# Arduino-Pro-Mini_Silk_1.net
KiCad netlist of a schematic drawn in EAGLE
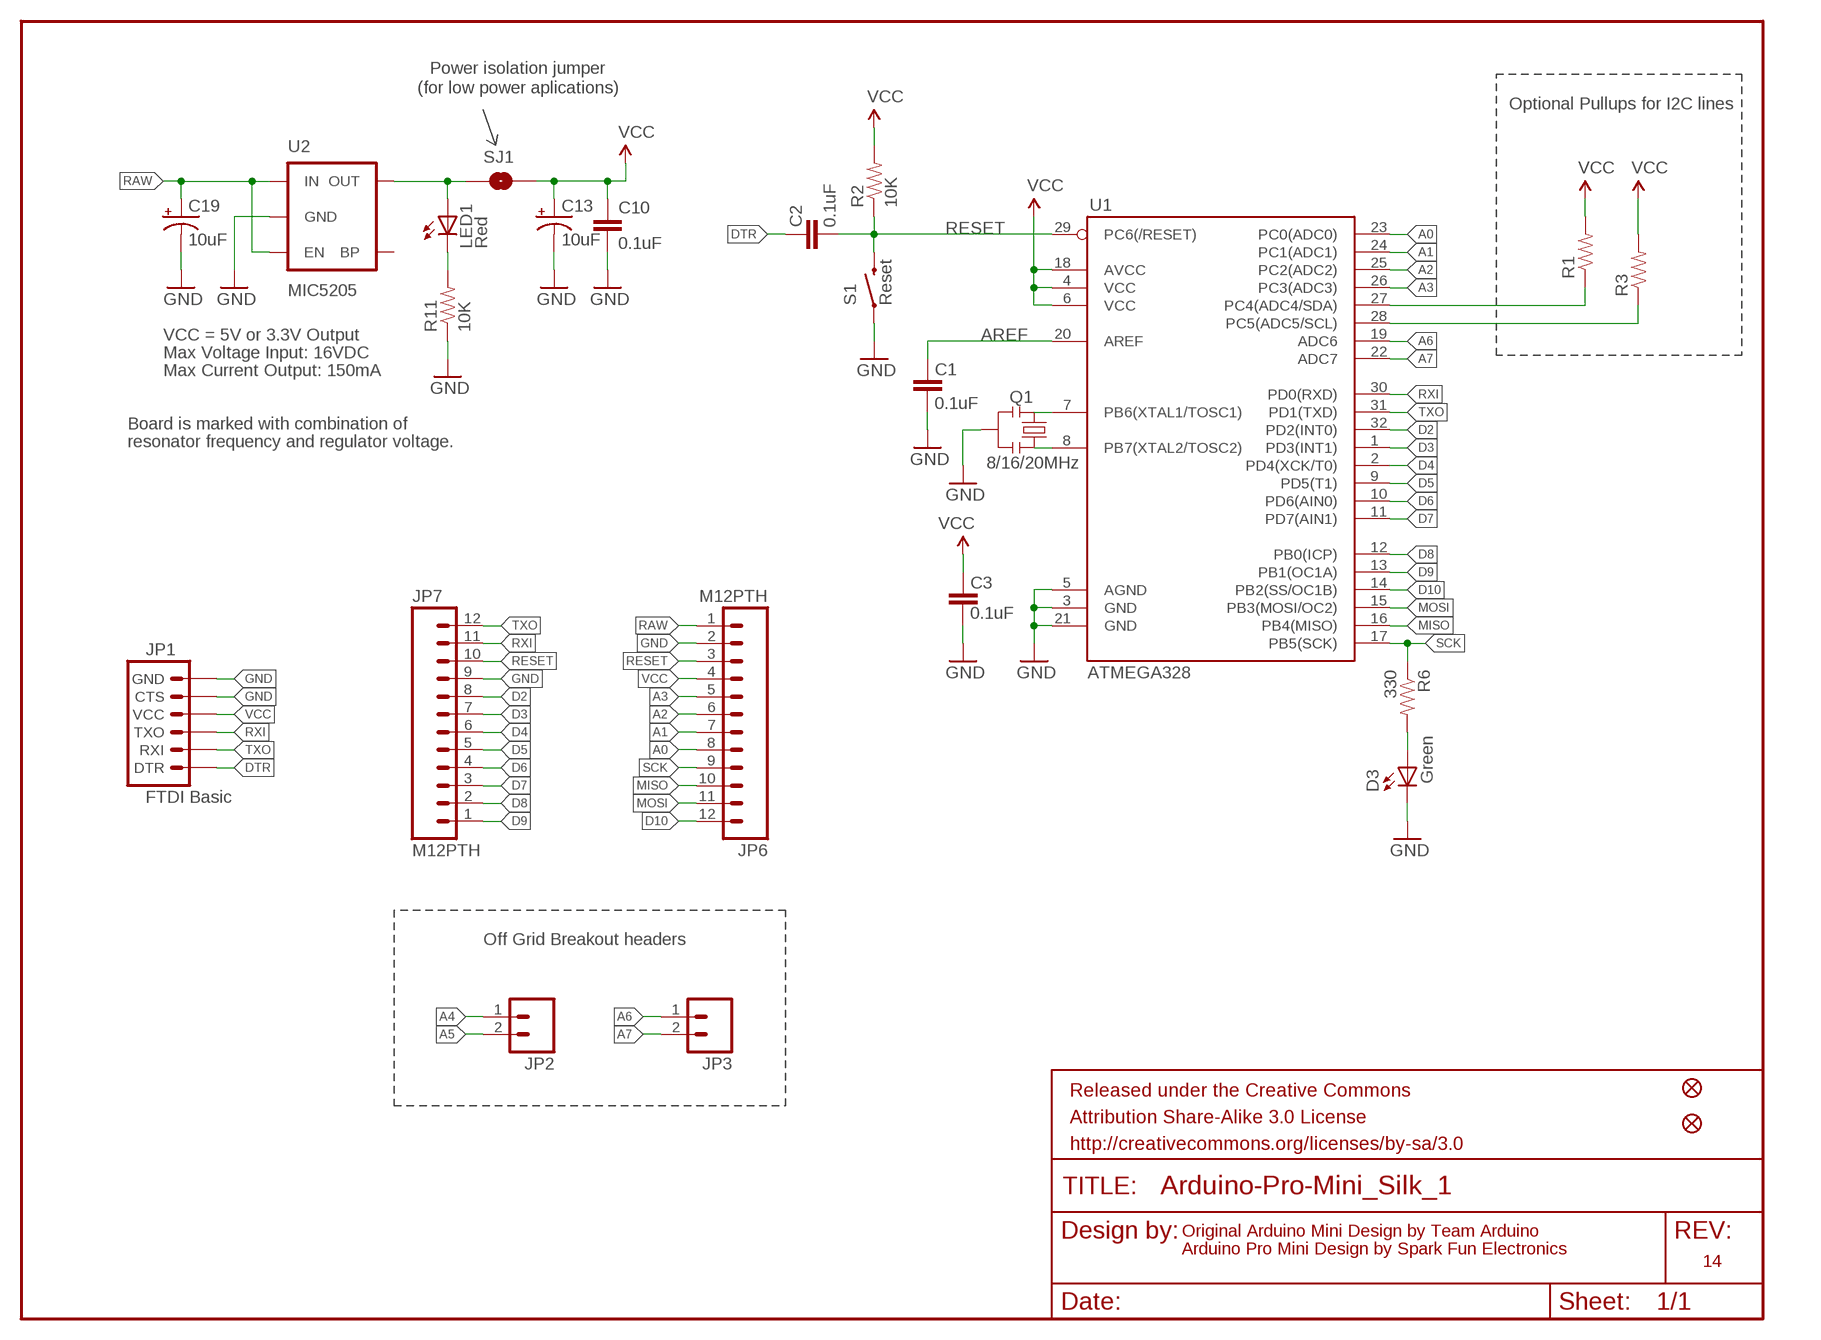
[diagram p0: schematic, sheet 1]

(export (version "E")
  (design (tool "Eeschema 10.0.6"))
  (components
    (comp (ref "C1")
      (value "0.1uF")
      (footprint "eagle-import:0603-CAP")
      (libsource (lib "eagle-import") (part "CAP0603-CAP"))
    )
    (comp (ref "C2")
      (value "0.1uF")
      (footprint "eagle-import:0603-CAP")
      (libsource (lib "eagle-import") (part "CAP0603-CAP"))
    )
    (comp (ref "C3")
      (value "0.1uF")
      (footprint "eagle-import:0603-CAP")
      (libsource (lib "eagle-import") (part "CAP0603-CAP"))
    )
    (comp (ref "C10")
      (value "0.1uF")
      (footprint "eagle-import:0603-CAP")
      (libsource (lib "eagle-import") (part "CAP0603-CAP"))
    )
    (comp (ref "C13")
      (value "10uF")
      (footprint "eagle-import:EIA3216")
      (libsource (lib "eagle-import") (part "CAP_POL1206"))
    )
    (comp (ref "C19")
      (value "10uF")
      (footprint "eagle-import:EIA3216")
      (libsource (lib "eagle-import") (part "CAP_POL1206"))
    )
    (comp (ref "D3")
      (value "Green")
      (footprint "eagle-import:0603-LED-ALT1")
      (libsource (lib "eagle-import") (part "LED"))
    )
    (comp (ref "FRAME1")
      (value "FRAME-LETTER")
      (footprint "eagle-import:CREATIVE_COMMONS")
      (libsource (lib "eagle-import") (part "FRAME-LETTER"))
    )
    (comp (ref "JP1")
      (value "FTDI Basic")
      (footprint "eagle-import:1X06")
      (libsource (lib "eagle-import") (part "ARDUINO_SERIAL_PROGRAMPTH"))
    )
    (comp (ref "JP2")
      (value "M02PTH")
      (footprint "eagle-import:1X02")
      (libsource (lib "eagle-import") (part "M02PTH"))
    )
    (comp (ref "JP3")
      (value "M02PTH")
      (footprint "eagle-import:1X02")
      (libsource (lib "eagle-import") (part "M02PTH"))
    )
    (comp (ref "JP5")
      (value "FIDUCIALUFIDUCIAL")
      (footprint "eagle-import:MICRO-FIDUCIAL")
      (libsource (lib "eagle-import") (part "FIDUCIALUFIDUCIAL"))
    )
    (comp (ref "JP6")
      (value "M12PTH")
      (footprint "eagle-import:1X12")
      (libsource (lib "eagle-import") (part "M12PTH"))
    )
    (comp (ref "JP7")
      (value "M12PTH")
      (footprint "eagle-import:1X12")
      (libsource (lib "eagle-import") (part "M12PTH"))
    )
    (comp (ref "JP8")
      (value "FIDUCIALUFIDUCIAL")
      (footprint "eagle-import:MICRO-FIDUCIAL")
      (libsource (lib "eagle-import") (part "FIDUCIALUFIDUCIAL"))
    )
    (comp (ref "LED1")
      (value "Red")
      (footprint "eagle-import:0603-LED-ALT1")
      (libsource (lib "eagle-import") (part "LED"))
    )
    (comp (ref "Q1")
      (value "8/16/20MHz")
      (footprint "eagle-import:RESONATOR-SMD-1_1")
      (libsource (lib "eagle-import") (part "RESONATOR1{colon}1"))
    )
    (comp (ref "R1")
      (value "RESISTOR0603-RES")
      (footprint "eagle-import:0603-RES")
      (libsource (lib "eagle-import") (part "RESISTOR0603-RES"))
    )
    (comp (ref "R2")
      (value "10K")
      (footprint "eagle-import:0603-RES")
      (libsource (lib "eagle-import") (part "RESISTOR0603-RES"))
    )
    (comp (ref "R3")
      (value "RESISTOR0603-RES")
      (footprint "eagle-import:0603-RES")
      (libsource (lib "eagle-import") (part "RESISTOR0603-RES"))
    )
    (comp (ref "R6")
      (value "330")
      (footprint "eagle-import:0603-RES")
      (libsource (lib "eagle-import") (part "RESISTOR0603-RES"))
    )
    (comp (ref "R11")
      (value "10K")
      (footprint "eagle-import:0603-RES")
      (libsource (lib "eagle-import") (part "RESISTOR0603-RES"))
    )
    (comp (ref "S1")
      (value "Reset")
      (footprint "eagle-import:TACTILE-SWITCH-SMD-ALT01")
      (libsource (lib "eagle-import") (part "SWITCH-MOMENTARY-2SMD-ALT01"))
    )
    (comp (ref "SJ1")
      (value "SOLDERJUMPERNC")
      (footprint "eagle-import:SJ_2S")
      (libsource (lib "eagle-import") (part "SOLDERJUMPERNC"))
    )
    (comp (ref "U1")
      (value "ATMEGA328")
      (footprint "eagle-import:TQFP32-08")
      (libsource (lib "eagle-import") (part "ATMEGA168"))
    )
    (comp (ref "U2")
      (value "MIC5205")
      (footprint "eagle-import:SOT23-5")
      (libsource (lib "eagle-import") (part "V_REG_LDOSMD"))
    )
  )
  (nets
    (net (code "1") (name "/AREF") (class "Default")
      (node (ref "C1") (pin "2") (pinfunction "2_2") (pintype "passive"))
      (node (ref "U1") (pin "20") (pinfunction "AREF_20") (pintype "bidirectional"))
    )
    (net (code "2") (name "A0") (class "Default")
      (node (ref "JP6") (pin "8") (pinfunction "8_8") (pintype "passive"))
      (node (ref "U1") (pin "23") (pinfunction "PC0(ADC0)_23") (pintype "bidirectional"))
    )
    (net (code "3") (name "A1") (class "Default")
      (node (ref "JP6") (pin "7") (pinfunction "7_7") (pintype "passive"))
      (node (ref "U1") (pin "24") (pinfunction "PC1(ADC1)_24") (pintype "bidirectional"))
    )
    (net (code "4") (name "A2") (class "Default")
      (node (ref "JP6") (pin "6") (pinfunction "6_6") (pintype "passive"))
      (node (ref "U1") (pin "25") (pinfunction "PC2(ADC2)_25") (pintype "bidirectional"))
    )
    (net (code "5") (name "A3") (class "Default")
      (node (ref "JP6") (pin "5") (pinfunction "5_5") (pintype "passive"))
      (node (ref "U1") (pin "26") (pinfunction "PC3(ADC3)_26") (pintype "bidirectional"))
    )
    (net (code "6") (name "A4") (class "Default")
      (node (ref "JP2") (pin "1") (pinfunction "1_1") (pintype "passive"))
      (node (ref "R1") (pin "1") (pinfunction "1_1") (pintype "passive"))
      (node (ref "U1") (pin "27") (pinfunction "PC4(ADC4/SDA)_27") (pintype "bidirectional"))
    )
    (net (code "7") (name "A5") (class "Default")
      (node (ref "JP2") (pin "2") (pinfunction "2_2") (pintype "passive"))
      (node (ref "R3") (pin "1") (pinfunction "1_1") (pintype "passive"))
      (node (ref "U1") (pin "28") (pinfunction "PC5(ADC5/SCL)_28") (pintype "bidirectional"))
    )
    (net (code "8") (name "A6") (class "Default")
      (node (ref "JP3") (pin "1") (pinfunction "1_1") (pintype "passive"))
      (node (ref "U1") (pin "19") (pinfunction "ADC6_19") (pintype "bidirectional"))
    )
    (net (code "9") (name "A7") (class "Default")
      (node (ref "JP3") (pin "2") (pinfunction "2_2") (pintype "passive"))
      (node (ref "U1") (pin "22") (pinfunction "ADC7_22") (pintype "bidirectional"))
    )
    (net (code "10") (name "D2") (class "Default")
      (node (ref "JP7") (pin "8") (pinfunction "8_8") (pintype "passive"))
      (node (ref "U1") (pin "32") (pinfunction "PD2(INT0)_32") (pintype "bidirectional"))
    )
    (net (code "11") (name "D3") (class "Default")
      (node (ref "JP7") (pin "7") (pinfunction "7_7") (pintype "passive"))
      (node (ref "U1") (pin "1") (pinfunction "PD3(INT1)_1") (pintype "bidirectional"))
    )
    (net (code "12") (name "D4") (class "Default")
      (node (ref "JP7") (pin "6") (pinfunction "6_6") (pintype "passive"))
      (node (ref "U1") (pin "2") (pinfunction "PD4(XCK/T0)_2") (pintype "bidirectional"))
    )
    (net (code "13") (name "D5") (class "Default")
      (node (ref "JP7") (pin "5") (pinfunction "5_5") (pintype "passive"))
      (node (ref "U1") (pin "9") (pinfunction "PD5(T1)_9") (pintype "bidirectional"))
    )
    (net (code "14") (name "D6") (class "Default")
      (node (ref "JP7") (pin "4") (pinfunction "4_4") (pintype "passive"))
      (node (ref "U1") (pin "10") (pinfunction "PD6(AIN0)_10") (pintype "bidirectional"))
    )
    (net (code "15") (name "D7") (class "Default")
      (node (ref "JP7") (pin "3") (pinfunction "3_3") (pintype "passive"))
      (node (ref "U1") (pin "11") (pinfunction "PD7(AIN1)_11") (pintype "bidirectional"))
    )
    (net (code "16") (name "D8") (class "Default")
      (node (ref "JP7") (pin "2") (pinfunction "2_2") (pintype "passive"))
      (node (ref "U1") (pin "12") (pinfunction "PB0(ICP)_12") (pintype "bidirectional"))
    )
    (net (code "17") (name "D9") (class "Default")
      (node (ref "JP7") (pin "1") (pinfunction "1_1") (pintype "passive"))
      (node (ref "U1") (pin "13") (pinfunction "PB1(OC1A)_13") (pintype "bidirectional"))
    )
    (net (code "18") (name "D10") (class "Default")
      (node (ref "JP6") (pin "12") (pinfunction "12_12") (pintype "passive"))
      (node (ref "U1") (pin "14") (pinfunction "PB2(SS/OC1B)_14") (pintype "bidirectional"))
    )
    (net (code "19") (name "DTR") (class "Default")
      (node (ref "C2") (pin "2") (pinfunction "2_2") (pintype "passive"))
      (node (ref "JP1") (pin "1") (pinfunction "DTR_1") (pintype "passive"))
    )
    (net (code "20") (name "GND") (class "Default")
      (node (ref "C1") (pin "1") (pinfunction "1_1") (pintype "passive"))
      (node (ref "C10") (pin "2") (pinfunction "2_2") (pintype "passive"))
      (node (ref "C13") (pin "C") (pinfunction "-_C") (pintype "passive"))
      (node (ref "C19") (pin "C") (pinfunction "-_C") (pintype "passive"))
      (node (ref "C3") (pin "1") (pinfunction "1_1") (pintype "passive"))
      (node (ref "D3") (pin "C") (pinfunction "C_C") (pintype "passive"))
      (node (ref "JP1") (pin "5") (pinfunction "CTS_5") (pintype "passive"))
      (node (ref "JP1") (pin "6") (pinfunction "GND_6") (pintype "passive"))
      (node (ref "JP6") (pin "2") (pinfunction "2_2") (pintype "passive"))
      (node (ref "JP7") (pin "9") (pinfunction "9_9") (pintype "passive"))
      (node (ref "Q1") (pin "2") (pinfunction "2_2") (pintype "passive"))
      (node (ref "R11") (pin "1") (pinfunction "1_1") (pintype "passive"))
      (node (ref "S1") (pin "1") (pinfunction "1_1") (pintype "passive"))
      (node (ref "S1") (pin "2") (pinfunction "1_2") (pintype "passive"))
      (node (ref "U1") (pin "21") (pinfunction "GND_21") (pintype "bidirectional"))
      (node (ref "U1") (pin "3") (pinfunction "GND_3") (pintype "bidirectional"))
      (node (ref "U1") (pin "5") (pinfunction "AGND_5") (pintype "bidirectional"))
      (node (ref "U2") (pin "2") (pinfunction "GND_2") (pintype "input"))
    )
    (net (code "21") (name "MISO") (class "Default")
      (node (ref "JP6") (pin "10") (pinfunction "10_10") (pintype "passive"))
      (node (ref "U1") (pin "16") (pinfunction "PB4(MISO)_16") (pintype "bidirectional"))
    )
    (net (code "22") (name "MOSI") (class "Default")
      (node (ref "JP6") (pin "11") (pinfunction "11_11") (pintype "passive"))
      (node (ref "U1") (pin "15") (pinfunction "PB3(MOSI/OC2)_15") (pintype "bidirectional"))
    )
    (net (code "23") (name "Net-(D3-PadA)") (class "Default")
      (node (ref "D3") (pin "A") (pinfunction "A_A") (pintype "passive"))
      (node (ref "R6") (pin "2") (pinfunction "2_2") (pintype "passive"))
    )
    (net (code "24") (name "Net-(LED1-PadC)") (class "Default")
      (node (ref "LED1") (pin "C") (pinfunction "C_C") (pintype "passive"))
      (node (ref "R11") (pin "2") (pinfunction "2_2") (pintype "passive"))
    )
    (net (code "25") (name "Net-(U1-PB6(XTAL1{slash}TOSC1))") (class "Default")
      (node (ref "Q1") (pin "1") (pinfunction "1_1") (pintype "passive"))
      (node (ref "U1") (pin "7") (pinfunction "PB6(XTAL1/TOSC1)_7") (pintype "bidirectional"))
    )
    (net (code "26") (name "Net-(U1-PB7(XTAL2{slash}TOSC2))") (class "Default")
      (node (ref "Q1") (pin "3") (pinfunction "3_3") (pintype "passive"))
      (node (ref "U1") (pin "8") (pinfunction "PB7(XTAL2/TOSC2)_8") (pintype "bidirectional"))
    )
    (net (code "27") (name "Net-(U2-OUT)") (class "Default")
      (node (ref "LED1") (pin "A") (pinfunction "A_A") (pintype "passive"))
      (node (ref "SJ1") (pin "1") (pinfunction "1_1") (pintype "passive"))
      (node (ref "U2") (pin "5") (pinfunction "OUT_5") (pintype "passive"))
    )
    (net (code "28") (name "RAW") (class "Default")
      (node (ref "C19") (pin "A") (pinfunction "+_A") (pintype "passive"))
      (node (ref "JP6") (pin "1") (pinfunction "1_1") (pintype "passive"))
      (node (ref "U2") (pin "1") (pinfunction "IN_1") (pintype "input"))
      (node (ref "U2") (pin "3") (pinfunction "EN_3") (pintype "input"))
    )
    (net (code "29") (name "RESET") (class "Default")
      (node (ref "C2") (pin "1") (pinfunction "1_1") (pintype "passive"))
      (node (ref "JP6") (pin "3") (pinfunction "3_3") (pintype "passive"))
      (node (ref "JP7") (pin "10") (pinfunction "10_10") (pintype "passive"))
      (node (ref "R2") (pin "1") (pinfunction "1_1") (pintype "passive"))
      (node (ref "S1") (pin "3") (pinfunction "2_3") (pintype "passive"))
      (node (ref "S1") (pin "4") (pinfunction "2_4") (pintype "passive"))
      (node (ref "U1") (pin "29") (pinfunction "PC6(/RESET)_29") (pintype "bidirectional"))
    )
    (net (code "30") (name "RXI") (class "Default")
      (node (ref "JP1") (pin "3") (pinfunction "TXO_3") (pintype "passive"))
      (node (ref "JP7") (pin "11") (pinfunction "11_11") (pintype "passive"))
      (node (ref "U1") (pin "30") (pinfunction "PD0(RXD)_30") (pintype "bidirectional"))
    )
    (net (code "31") (name "SCK") (class "Default")
      (node (ref "JP6") (pin "9") (pinfunction "9_9") (pintype "passive"))
      (node (ref "R6") (pin "1") (pinfunction "1_1") (pintype "passive"))
      (node (ref "U1") (pin "17") (pinfunction "PB5(SCK)_17") (pintype "bidirectional"))
    )
    (net (code "32") (name "TXO") (class "Default")
      (node (ref "JP1") (pin "2") (pinfunction "RXI_2") (pintype "passive"))
      (node (ref "JP7") (pin "12") (pinfunction "12_12") (pintype "passive"))
      (node (ref "U1") (pin "31") (pinfunction "PD1(TXD)_31") (pintype "bidirectional"))
    )
    (net (code "33") (name "VCC") (class "Default")
      (node (ref "C10") (pin "1") (pinfunction "1_1") (pintype "passive"))
      (node (ref "C13") (pin "A") (pinfunction "+_A") (pintype "passive"))
      (node (ref "C3") (pin "2") (pinfunction "2_2") (pintype "passive"))
      (node (ref "JP1") (pin "4") (pinfunction "VCC_4") (pintype "passive"))
      (node (ref "JP6") (pin "4") (pinfunction "4_4") (pintype "passive"))
      (node (ref "R1") (pin "2") (pinfunction "2_2") (pintype "passive"))
      (node (ref "R2") (pin "2") (pinfunction "2_2") (pintype "passive"))
      (node (ref "R3") (pin "2") (pinfunction "2_2") (pintype "passive"))
      (node (ref "SJ1") (pin "2") (pinfunction "2_2") (pintype "passive"))
      (node (ref "U1") (pin "18") (pinfunction "AVCC_18") (pintype "bidirectional"))
      (node (ref "U1") (pin "4") (pinfunction "VCC_4") (pintype "bidirectional"))
      (node (ref "U1") (pin "6") (pinfunction "VCC_6") (pintype "bidirectional"))
    )
    (net (code "34") (name "unconnected-(U2-BP-Pad4)") (class "Default")
      (node (ref "U2") (pin "4") (pinfunction "BP_4") (pintype "input"))
    )
  )
)
